# MySens-GWeasySensRS485-V01-009.net
KiCad netlist of a schematic drawn in EAGLE
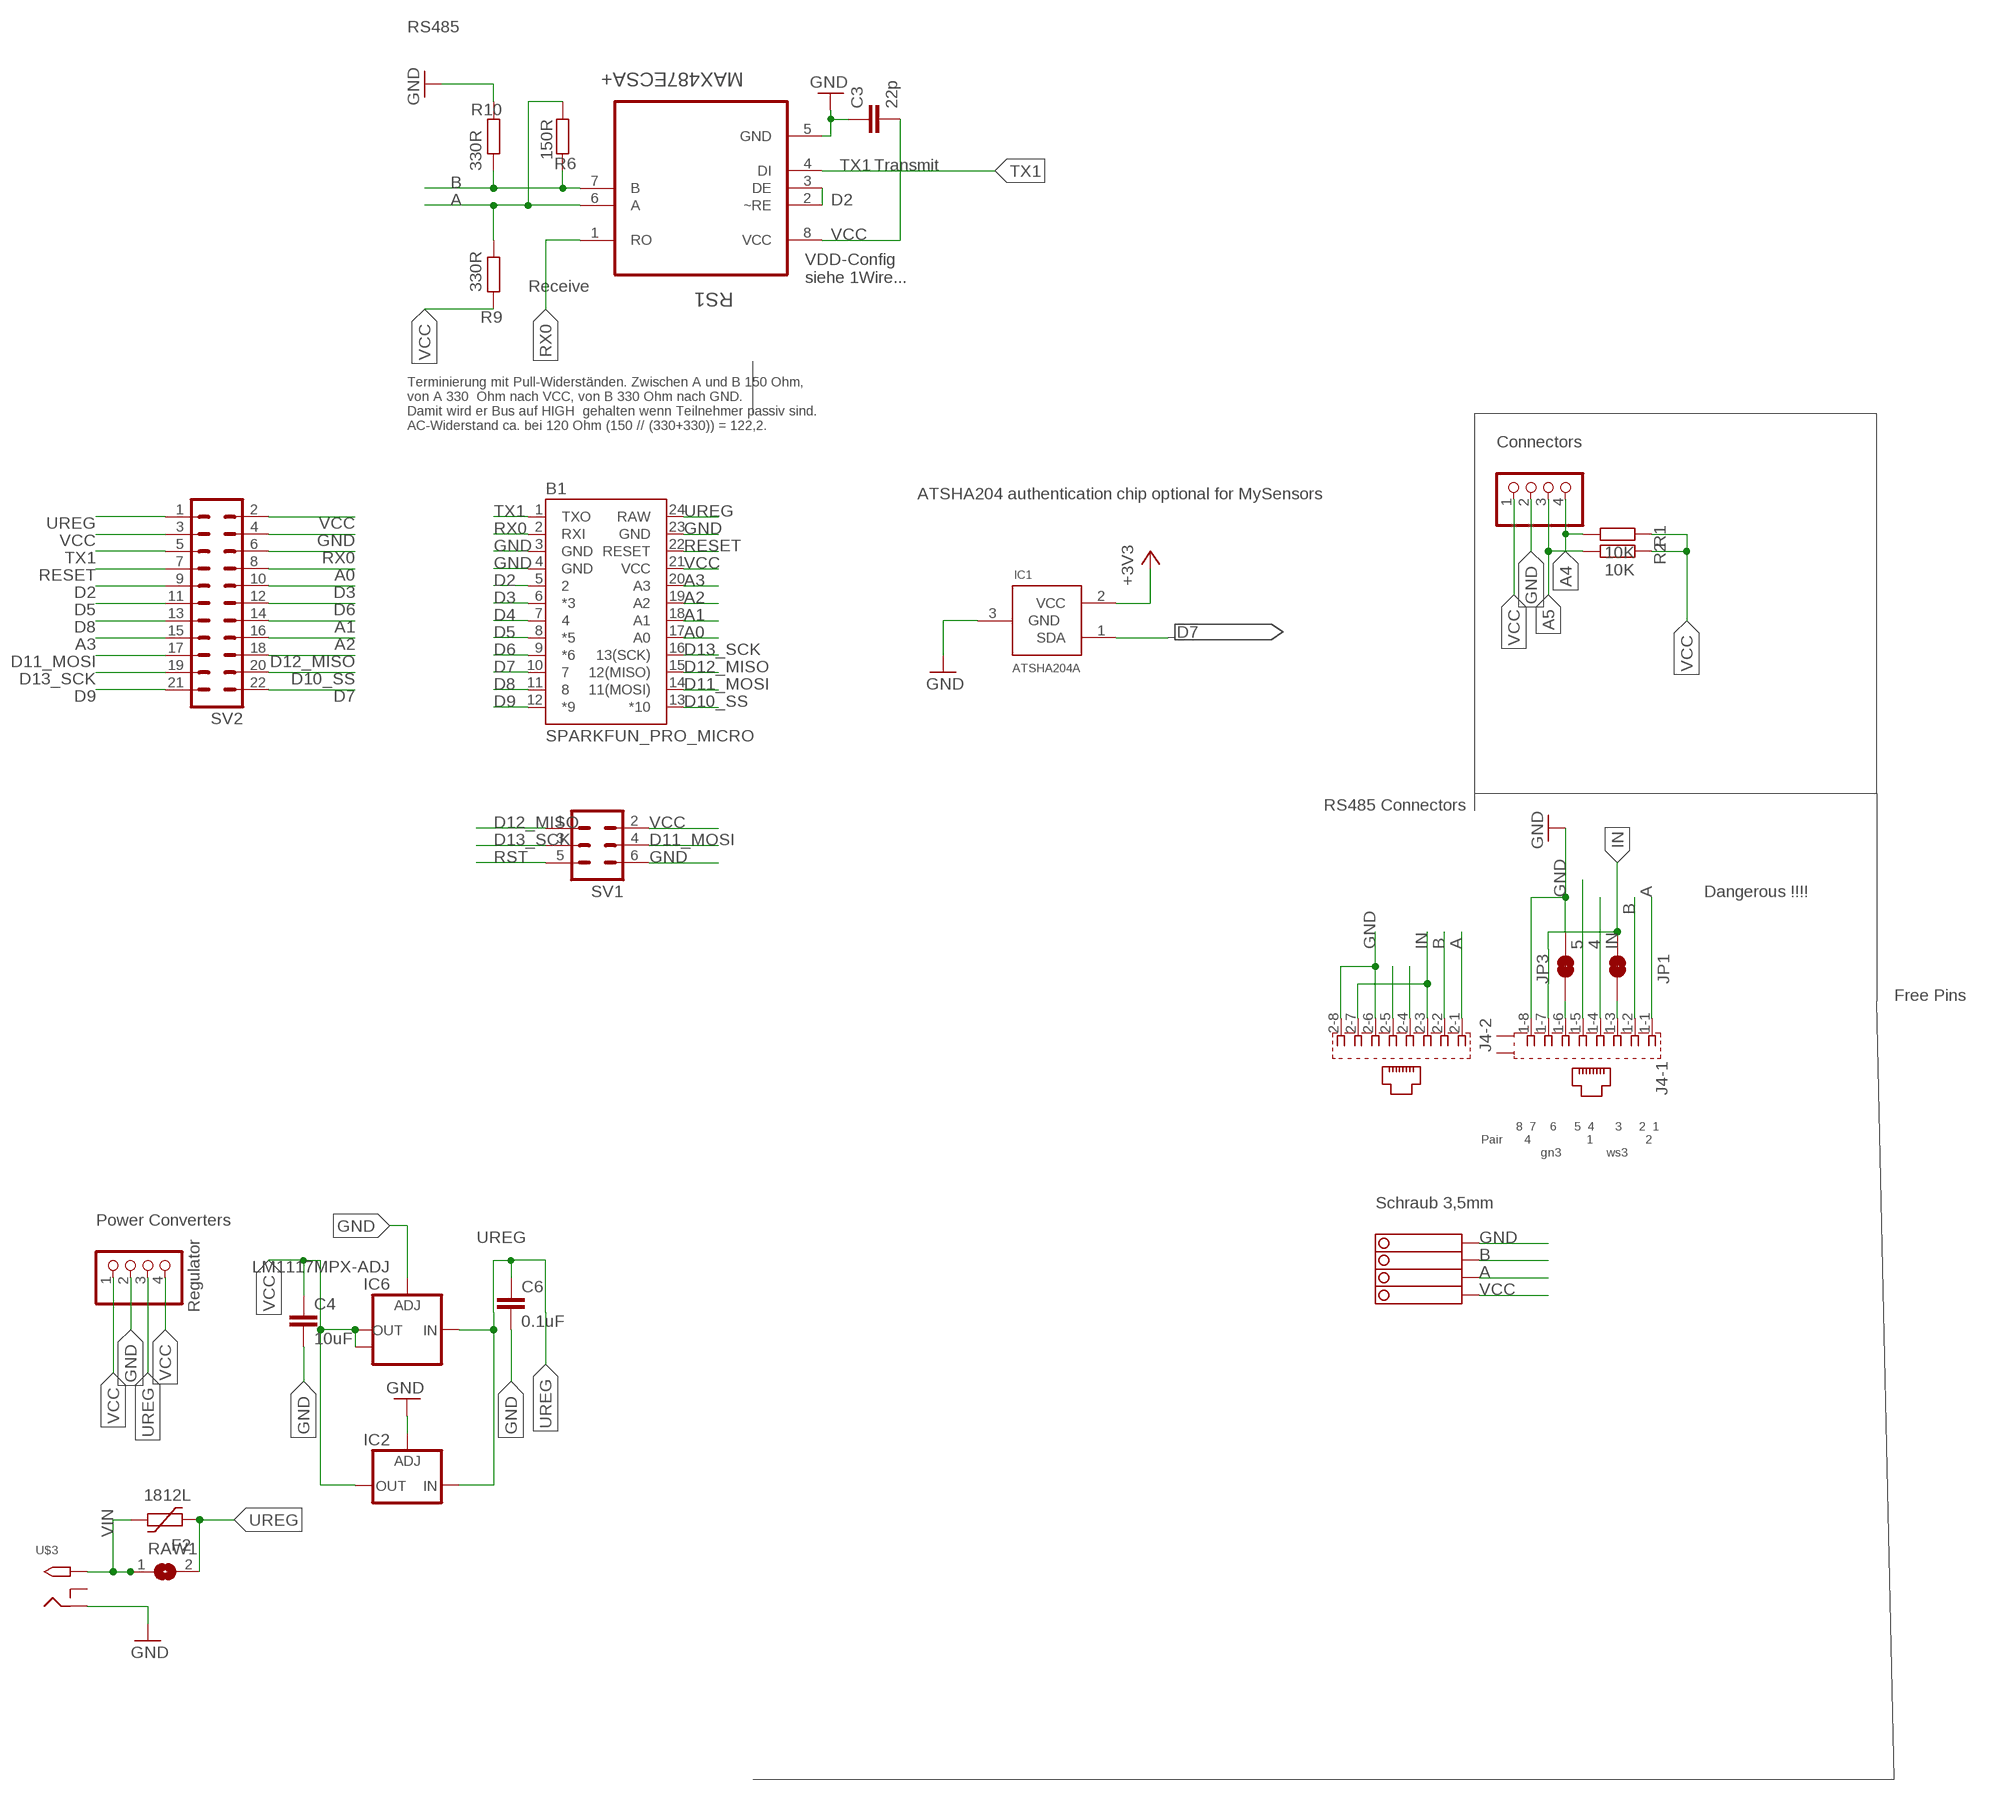
[diagram p0: schematic, sheet 1]

(export (version "E")
  (design (tool "Eeschema 10.0.6"))
  (components
    (comp (ref "B1")
      (value "SPARKFUN_PRO_MICRO")
      (footprint "eagle-import:SPARKFUN_PRO_MICRO")
      (libsource (lib "eagle-import") (part "SPARKFUN_PRO_MICRO"))
    )
    (comp (ref "C3")
      (value "22p")
      (footprint "eagle-import:C0805")
      (libsource (lib "eagle-import") (part "C-EUC0805"))
    )
    (comp (ref "C4")
      (value "10uF")
      (footprint "eagle-import:C1210")
      (libsource (lib "eagle-import") (part "C-EUC1210"))
    )
    (comp (ref "C6")
      (value "0.1uF")
      (footprint "eagle-import:C1206")
      (libsource (lib "eagle-import") (part "C-EUC1206"))
    )
    (comp (ref "F2")
      (value "1812L")
      (footprint "eagle-import:1812L")
      (libsource (lib "eagle-import") (part "1812L"))
    )
    (comp (ref "IC1")
      (value "ATSHA204A")
      (footprint "eagle-import:SOT23")
      (libsource (lib "eagle-import") (part "ATSHA204A"))
    )
    (comp (ref "IC2")
      (value "LD117ADT50TR")
      (footprint "eagle-import:DPACK")
      (libsource (lib "eagle-import") (part "LD117A?DT50TR"))
    )
    (comp (ref "IC6")
      (value "LM1117MPX-ADJ")
      (footprint "eagle-import:SOT223")
      (libsource (lib "eagle-import") (part "LM1117MPX-ADJ"))
    )
    (comp (ref "J4")
      (value "RJ45_2X_NARROW_SHILDPINS_NOCASE")
      (footprint "eagle-import:RJ45_2X_NARROW_SHILDPINS_NOCASE")
      (libsource (lib "eagle-import") (part "RJ45_2X_NARROW_SHILDPINS_NOCASE"))
    )
    (comp (ref "JP1")
      (value "JUMPER-SMT_2_NC_TRACE_SILK")
      (footprint "eagle-import:SMT-JUMPER_2_NC_TRACE_SILK")
      (libsource (lib "eagle-import") (part "JUMPER-SMT_2_NC_TRACE_SILK"))
    )
    (comp (ref "JP3")
      (value "JUMPER-SMT_2_NC_TRACE_SILK")
      (footprint "eagle-import:SMT-JUMPER_2_NC_TRACE_SILK")
      (libsource (lib "eagle-import") (part "JUMPER-SMT_2_NC_TRACE_SILK"))
    )
    (comp (ref "JP10")
      (value "PINHD-1X04_2.54-S")
      (footprint "eagle-import:1X04-S")
      (libsource (lib "eagle-import") (part "PINHD-1X04_2.54-S"))
    )
    (comp (ref "R1")
      (value "10K")
      (footprint "eagle-import:R0805")
      (libsource (lib "eagle-import") (part "R-EU_R0805"))
    )
    (comp (ref "R2")
      (value "10K")
      (footprint "eagle-import:R0805")
      (libsource (lib "eagle-import") (part "R-EU_R0805"))
    )
    (comp (ref "R6")
      (value "150R")
      (footprint "eagle-import:R0805")
      (libsource (lib "eagle-import") (part "R-EU_R0805"))
    )
    (comp (ref "R9")
      (value "330R")
      (footprint "eagle-import:R0805")
      (libsource (lib "eagle-import") (part "R-EU_R0805"))
    )
    (comp (ref "R10")
      (value "330R")
      (footprint "eagle-import:R0805")
      (libsource (lib "eagle-import") (part "R-EU_R0805"))
    )
    (comp (ref "RAW1")
      (value "SJ")
      (footprint "eagle-import:SJ")
      (libsource (lib "eagle-import") (part "SJ"))
    )
    (comp (ref "RS1")
      (value "MAX487ECSA+")
      (footprint "eagle-import:SOIC127P600X175-8N")
      (libsource (lib "eagle-import") (part "MAX487ECSA+"))
    )
    (comp (ref "STEPDWN")
      (value "PINHD-1X04_2.54-S")
      (footprint "eagle-import:1X04-S")
      (libsource (lib "eagle-import") (part "PINHD-1X04_2.54-S"))
    )
    (comp (ref "SV1")
      (value "MA03-2")
      (footprint "eagle-import:MA03-2")
      (libsource (lib "eagle-import") (part "MA03-2"))
    )
    (comp (ref "SV2")
      (value "MA11-2")
      (footprint "eagle-import:MA11-2")
      (libsource (lib "eagle-import") (part "MA11-2"))
    )
    (comp (ref "U$3")
      (value "2.1MMJACKTHM")
      (footprint "eagle-import:PJ-102A")
      (libsource (lib "eagle-import") (part "2.1MMJACKTHM"))
    )
    (comp (ref "X4")
      (value "1751264")
      (footprint "eagle-import:1751264")
      (libsource (lib "eagle-import") (part "1751264"))
    )
  )
  (nets
    (net (code "1") (name "+3V3") (class "Default")
      (node (ref "IC1") (pin "2") (pinfunction "VCC_2") (pintype "bidirectional"))
    )
    (net (code "2") (name "/4") (class "Default")
      (node (ref "J4") (pin "1-4") (pinfunction "4_1-4") (pintype "passive"))
    )
    (net (code "3") (name "/5") (class "Default")
      (node (ref "J4") (pin "1-5") (pinfunction "5_1-5") (pintype "passive"))
    )
    (net (code "4") (name "/A") (class "Default")
      (node (ref "J4") (pin "1-1") (pinfunction "1_1-1") (pintype "passive"))
      (node (ref "J4") (pin "2-1") (pinfunction "1_2-1") (pintype "passive"))
      (node (ref "R6") (pin "1") (pinfunction "1_1") (pintype "passive"))
      (node (ref "R9") (pin "2") (pinfunction "2_2") (pintype "passive"))
      (node (ref "RS1") (pin "6") (pinfunction "A_6") (pintype "bidirectional"))
      (node (ref "X4") (pin "2") (pinfunction "K_2") (pintype "passive"))
    )
    (net (code "5") (name "/A0") (class "Default")
      (node (ref "B1") (pin "17") (pinfunction "A0_17") (pintype "bidirectional"))
      (node (ref "SV2") (pin "8") (pinfunction "8_8") (pintype "passive"))
    )
    (net (code "6") (name "/A1") (class "Default")
      (node (ref "B1") (pin "18") (pinfunction "A1_18") (pintype "bidirectional"))
      (node (ref "SV2") (pin "14") (pinfunction "14_14") (pintype "passive"))
    )
    (net (code "7") (name "/A2") (class "Default")
      (node (ref "B1") (pin "19") (pinfunction "A2_19") (pintype "bidirectional"))
      (node (ref "SV2") (pin "16") (pinfunction "16_16") (pintype "passive"))
    )
    (net (code "8") (name "/A3") (class "Default")
      (node (ref "B1") (pin "20") (pinfunction "A3_20") (pintype "bidirectional"))
      (node (ref "SV2") (pin "15") (pinfunction "15_15") (pintype "passive"))
    )
    (net (code "9") (name "/B") (class "Default")
      (node (ref "J4") (pin "1-2") (pinfunction "2_1-2") (pintype "passive"))
      (node (ref "J4") (pin "2-2") (pinfunction "2_2-2") (pintype "passive"))
      (node (ref "R10") (pin "1") (pinfunction "1_1") (pintype "passive"))
      (node (ref "R6") (pin "2") (pinfunction "2_2") (pintype "passive"))
      (node (ref "RS1") (pin "7") (pinfunction "B_7") (pintype "bidirectional"))
      (node (ref "X4") (pin "3") (pinfunction "K_3") (pintype "passive"))
    )
    (net (code "10") (name "/D2") (class "Default")
      (node (ref "B1") (pin "5") (pinfunction "2_5") (pintype "bidirectional"))
      (node (ref "RS1") (pin "2") (pinfunction "~{RE}_2") (pintype "input"))
      (node (ref "RS1") (pin "3") (pinfunction "DE_3") (pintype "input"))
      (node (ref "SV2") (pin "9") (pinfunction "9_9") (pintype "passive"))
    )
    (net (code "11") (name "/D3") (class "Default")
      (node (ref "B1") (pin "6") (pinfunction "*3_6") (pintype "bidirectional"))
      (node (ref "SV2") (pin "10") (pinfunction "10_10") (pintype "passive"))
    )
    (net (code "12") (name "/D4") (class "Default")
      (node (ref "B1") (pin "7") (pinfunction "4_7") (pintype "bidirectional"))
    )
    (net (code "13") (name "/D5") (class "Default")
      (node (ref "B1") (pin "8") (pinfunction "*5_8") (pintype "bidirectional"))
      (node (ref "SV2") (pin "11") (pinfunction "11_11") (pintype "passive"))
    )
    (net (code "14") (name "/D6") (class "Default")
      (node (ref "B1") (pin "9") (pinfunction "*6_9") (pintype "bidirectional"))
      (node (ref "SV2") (pin "12") (pinfunction "12_12") (pintype "passive"))
    )
    (net (code "15") (name "/D7") (class "Default")
      (node (ref "B1") (pin "10") (pinfunction "7_10") (pintype "bidirectional"))
      (node (ref "IC1") (pin "1") (pinfunction "SDA_1") (pintype "bidirectional"))
      (node (ref "SV2") (pin "22") (pinfunction "22_22") (pintype "passive"))
    )
    (net (code "16") (name "/D8") (class "Default")
      (node (ref "B1") (pin "11") (pinfunction "8_11") (pintype "bidirectional"))
      (node (ref "SV2") (pin "13") (pinfunction "13_13") (pintype "passive"))
    )
    (net (code "17") (name "/D9") (class "Default")
      (node (ref "B1") (pin "12") (pinfunction "*9_12") (pintype "bidirectional"))
      (node (ref "SV2") (pin "21") (pinfunction "21_21") (pintype "passive"))
    )
    (net (code "18") (name "/D10_SS") (class "Default")
      (node (ref "B1") (pin "13") (pinfunction "*10_13") (pintype "bidirectional"))
      (node (ref "SV2") (pin "20") (pinfunction "20_20") (pintype "passive"))
    )
    (net (code "19") (name "/D11_MOSI") (class "Default")
      (node (ref "B1") (pin "14") (pinfunction "11(MOSI)_14") (pintype "bidirectional"))
      (node (ref "SV1") (pin "4") (pinfunction "4_4") (pintype "passive"))
      (node (ref "SV2") (pin "17") (pinfunction "17_17") (pintype "passive"))
    )
    (net (code "20") (name "/D12_MISO") (class "Default")
      (node (ref "B1") (pin "15") (pinfunction "12(MISO)_15") (pintype "bidirectional"))
      (node (ref "SV1") (pin "1") (pinfunction "1_1") (pintype "passive"))
      (node (ref "SV2") (pin "18") (pinfunction "18_18") (pintype "passive"))
    )
    (net (code "21") (name "/D13_SCK") (class "Default")
      (node (ref "B1") (pin "16") (pinfunction "13(SCK)_16") (pintype "bidirectional"))
      (node (ref "SV1") (pin "3") (pinfunction "3_3") (pintype "passive"))
      (node (ref "SV2") (pin "19") (pinfunction "19_19") (pintype "passive"))
    )
    (net (code "22") (name "/RESET") (class "Default")
      (node (ref "B1") (pin "22") (pinfunction "RESET_22") (pintype "bidirectional"))
      (node (ref "SV2") (pin "7") (pinfunction "7_7") (pintype "passive"))
    )
    (net (code "23") (name "/RST") (class "Default")
      (node (ref "SV1") (pin "5") (pinfunction "5_5") (pintype "passive"))
    )
    (net (code "24") (name "/VIN") (class "Default")
      (node (ref "F2") (pin "P$2") (pinfunction "2_P$2") (pintype "passive"))
      (node (ref "RAW1") (pin "1") (pinfunction "1_1") (pintype "passive"))
      (node (ref "U$3") (pin "TIP") (pinfunction "TIP_TIP") (pintype "bidirectional"))
    )
    (net (code "25") (name "A4") (class "Default")
      (node (ref "JP10") (pin "4") (pinfunction "4_4") (pintype "passive"))
      (node (ref "R1") (pin "2") (pinfunction "2_2") (pintype "passive"))
    )
    (net (code "26") (name "A5") (class "Default")
      (node (ref "JP10") (pin "3") (pinfunction "3_3") (pintype "passive"))
      (node (ref "R2") (pin "2") (pinfunction "2_2") (pintype "passive"))
    )
    (net (code "27") (name "GND") (class "Default")
      (node (ref "B1") (pin "23") (pinfunction "GND_23") (pintype "power_in"))
      (node (ref "B1") (pin "3") (pinfunction "GND_3") (pintype "power_in"))
      (node (ref "B1") (pin "4") (pinfunction "GND_4") (pintype "power_in"))
      (node (ref "C3") (pin "1") (pinfunction "1_1") (pintype "passive"))
      (node (ref "C4") (pin "2") (pinfunction "2_2") (pintype "passive"))
      (node (ref "C6") (pin "2") (pinfunction "2_2") (pintype "passive"))
      (node (ref "IC1") (pin "3") (pinfunction "GND_3") (pintype "bidirectional"))
      (node (ref "IC2") (pin "1") (pinfunction "ADJ_1") (pintype "input"))
      (node (ref "IC6") (pin "1") (pinfunction "ADJ_1") (pintype "input"))
      (node (ref "J4") (pin "1-8") (pinfunction "8_1-8") (pintype "passive"))
      (node (ref "J4") (pin "2-6") (pinfunction "6_2-6") (pintype "passive"))
      (node (ref "J4") (pin "2-8") (pinfunction "8_2-8") (pintype "passive"))
      (node (ref "JP10") (pin "2") (pinfunction "2_2") (pintype "passive"))
      (node (ref "JP3") (pin "2") (pinfunction "2_2") (pintype "passive"))
      (node (ref "R10") (pin "2") (pinfunction "2_2") (pintype "passive"))
      (node (ref "RS1") (pin "5") (pinfunction "GND_5") (pintype "passive"))
      (node (ref "STEPDWN") (pin "2") (pinfunction "2_2") (pintype "passive"))
      (node (ref "SV1") (pin "6") (pinfunction "6_6") (pintype "passive"))
      (node (ref "SV2") (pin "4") (pinfunction "4_4") (pintype "passive"))
      (node (ref "U$3") (pin "RING") (pinfunction "RING_RING") (pintype "bidirectional"))
      (node (ref "X4") (pin "4") (pinfunction "K_4") (pintype "passive"))
    )
    (net (code "28") (name "IN") (class "Default")
      (node (ref "J4") (pin "1-7") (pinfunction "7_1-7") (pintype "passive"))
      (node (ref "J4") (pin "2-3") (pinfunction "3_2-3") (pintype "passive"))
      (node (ref "J4") (pin "2-7") (pinfunction "7_2-7") (pintype "passive"))
      (node (ref "JP1") (pin "2") (pinfunction "2_2") (pintype "passive"))
    )
    (net (code "29") (name "Net-(J4A-3)") (class "Default")
      (node (ref "J4") (pin "1-3") (pinfunction "3_1-3") (pintype "passive"))
      (node (ref "JP1") (pin "1") (pinfunction "1_1") (pintype "passive"))
    )
    (net (code "30") (name "Net-(J4A-6)") (class "Default")
      (node (ref "J4") (pin "1-6") (pinfunction "6_1-6") (pintype "passive"))
      (node (ref "JP3") (pin "1") (pinfunction "1_1") (pintype "passive"))
    )
    (net (code "31") (name "RX0") (class "Default")
      (node (ref "B1") (pin "2") (pinfunction "RXI_2") (pintype "bidirectional"))
      (node (ref "RS1") (pin "1") (pinfunction "RO_1") (pintype "output"))
      (node (ref "SV2") (pin "6") (pinfunction "6_6") (pintype "passive"))
    )
    (net (code "32") (name "TX1") (class "Default")
      (node (ref "B1") (pin "1") (pinfunction "TXO_1") (pintype "bidirectional"))
      (node (ref "RS1") (pin "4") (pinfunction "DI_4") (pintype "input"))
      (node (ref "SV2") (pin "5") (pinfunction "5_5") (pintype "passive"))
    )
    (net (code "33") (name "UREG") (class "Default")
      (node (ref "B1") (pin "24") (pinfunction "RAW_24") (pintype "power_in"))
      (node (ref "C6") (pin "1") (pinfunction "1_1") (pintype "passive"))
      (node (ref "F2") (pin "P$1") (pinfunction "1_P$1") (pintype "passive"))
      (node (ref "IC2") (pin "3") (pinfunction "IN_3") (pintype "input"))
      (node (ref "IC6") (pin "3") (pinfunction "IN_3") (pintype "input"))
      (node (ref "RAW1") (pin "2") (pinfunction "2_2") (pintype "passive"))
      (node (ref "STEPDWN") (pin "3") (pinfunction "3_3") (pintype "passive"))
      (node (ref "SV2") (pin "1") (pinfunction "1_1") (pintype "passive"))
    )
    (net (code "34") (name "VCC") (class "Default")
      (node (ref "B1") (pin "21") (pinfunction "VCC_21") (pintype "power_in"))
      (node (ref "C3") (pin "2") (pinfunction "2_2") (pintype "passive"))
      (node (ref "C4") (pin "1") (pinfunction "1_1") (pintype "passive"))
      (node (ref "IC2") (pin "4") (pinfunction "OUT_4") (pintype "passive"))
      (node (ref "IC6") (pin "2") (pinfunction "OUT_2") (pintype "passive"))
      (node (ref "IC6") (pin "TAB") (pinfunction "OUT1_TAB") (pintype "passive"))
      (node (ref "JP10") (pin "1") (pinfunction "1_1") (pintype "passive"))
      (node (ref "R1") (pin "1") (pinfunction "1_1") (pintype "passive"))
      (node (ref "R2") (pin "1") (pinfunction "1_1") (pintype "passive"))
      (node (ref "R9") (pin "1") (pinfunction "1_1") (pintype "passive"))
      (node (ref "RS1") (pin "8") (pinfunction "VCC_8") (pintype "power_in"))
      (node (ref "STEPDWN") (pin "1") (pinfunction "1_1") (pintype "passive"))
      (node (ref "STEPDWN") (pin "4") (pinfunction "4_4") (pintype "passive"))
      (node (ref "SV1") (pin "2") (pinfunction "2_2") (pintype "passive"))
      (node (ref "SV2") (pin "2") (pinfunction "2_2") (pintype "passive"))
      (node (ref "SV2") (pin "3") (pinfunction "3_3") (pintype "passive"))
      (node (ref "X4") (pin "1") (pinfunction "K_1") (pintype "passive"))
    )
    (net (code "35") (name "unconnected-(J4A-S1-PadG1)") (class "Default")
      (node (ref "J4") (pin "G1") (pinfunction "S1_G1") (pintype "passive"))
    )
    (net (code "36") (name "unconnected-(J4A-S2-PadG3)") (class "Default")
      (node (ref "J4") (pin "G3") (pinfunction "S2_G3") (pintype "passive"))
    )
    (net (code "37") (name "unconnected-(J4B-4-Pad2-4)") (class "Default")
      (node (ref "J4") (pin "2-4") (pinfunction "4_2-4") (pintype "passive"))
    )
    (net (code "38") (name "unconnected-(J4B-5-Pad2-5)") (class "Default")
      (node (ref "J4") (pin "2-5") (pinfunction "5_2-5") (pintype "passive"))
    )
    (net (code "39") (name "unconnected-(U$3-PadRING_SW)") (class "Default")
      (node (ref "U$3") (pin "RING_SW") (pinfunction "RING_SW_RING_SW") (pintype "bidirectional"))
    )
  )
)
